# BQ24250.net
KiCad netlist of a schematic drawn in Altium Designer
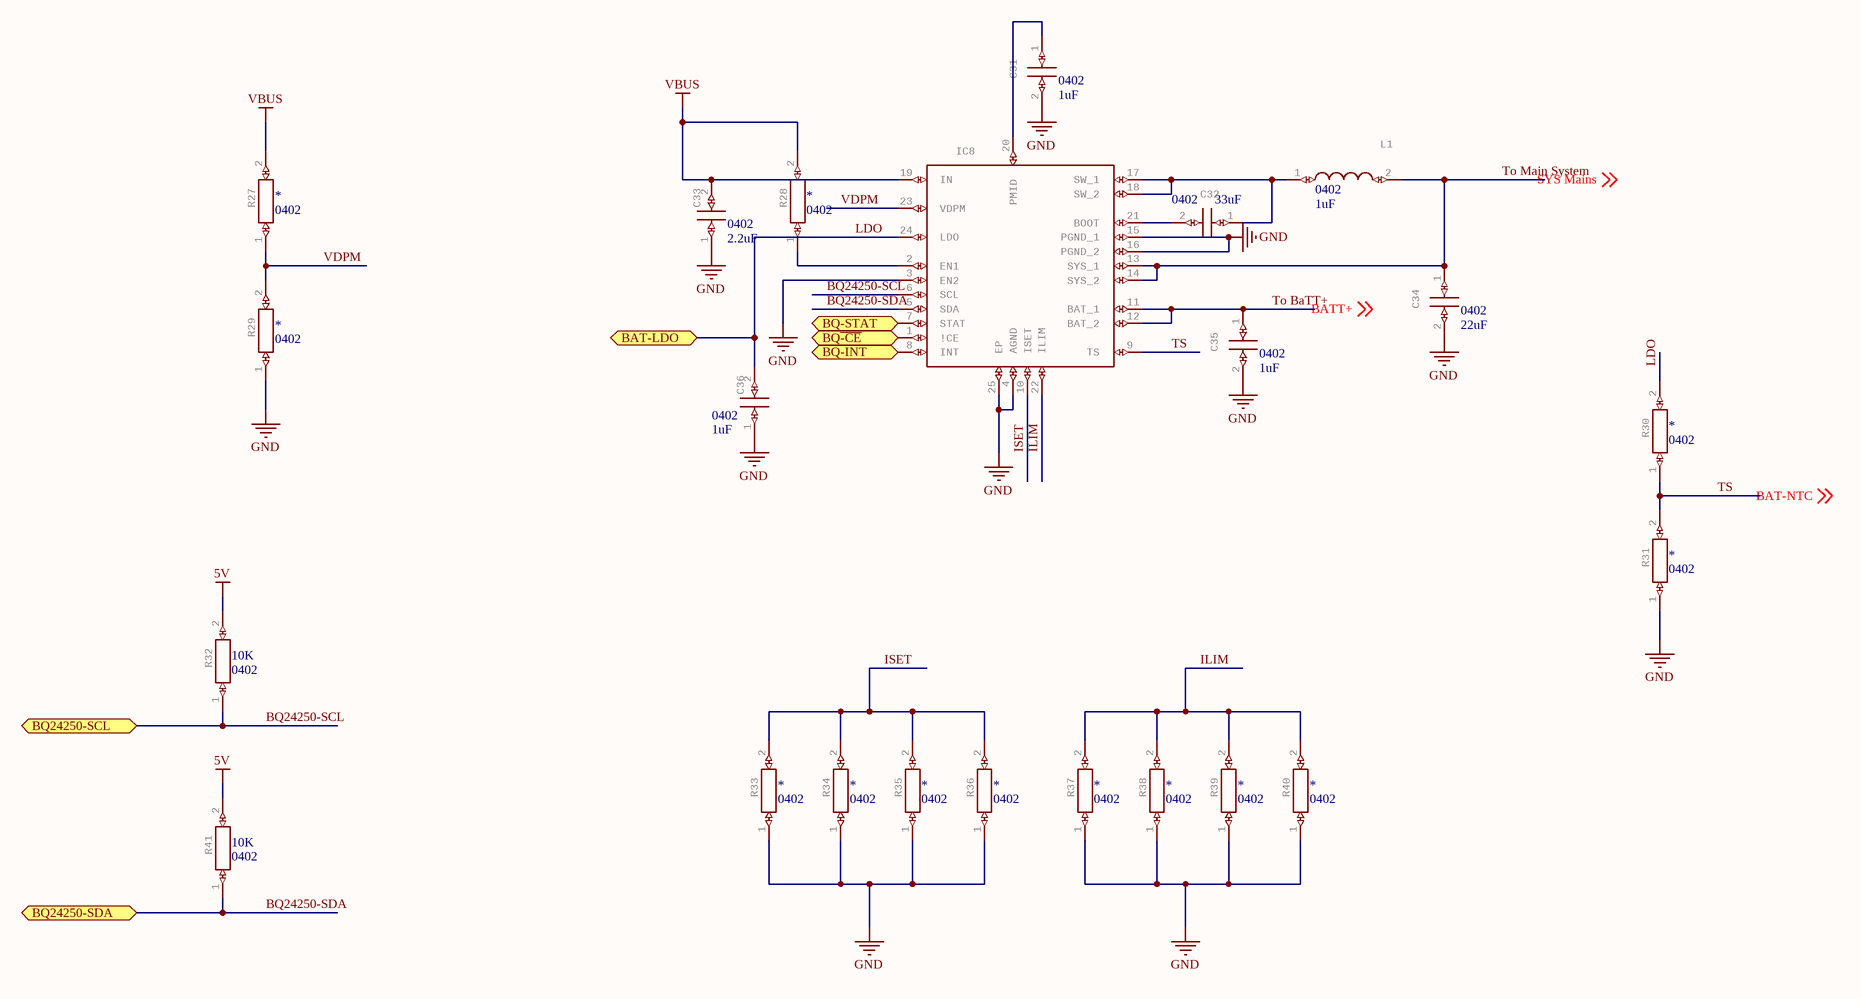
[diagram p0: BQ24250.SchDoc]

(export (version "E")
  (design (tool "Eeschema 10.0.6"))
  (components
    (comp (ref "C31")
      (value "1uF")
      (footprint "CAPC1005X56N")
      (fields
        (field (name "MANUFACTURER_PART_NUMBER") "04025C104KAT2A")
        (field (name "MOUSER_PART_NUMBER") "581-04025C104KAT2A")
        (field (name "PACKAGE") "0402")
        (field (name "Comment") "Multilayer Ceramic Capacitors MLCC - SMD/SMT 50V .1uF X7R 0402 10% Tol   Source:  Datasheet")
      )
      (libsource (lib "C0402-GP") (part "04025C104KAT2A"))
    )
    (comp (ref "C32")
      (value "33uF")
      (footprint "CAPC1005X56N")
      (fields
        (field (name "MANUFACTURER_PART_NUMBER") "04025C104KAT2A")
        (field (name "MOUSER_PART_NUMBER") "581-04025C104KAT2A")
        (field (name "PACKAGE") "0402")
        (field (name "Comment") "Multilayer Ceramic Capacitors MLCC - SMD/SMT 50V .1uF X7R 0402 10% Tol   Source:  Datasheet")
      )
      (libsource (lib "C0402-GP") (part "04025C104KAT2A"))
    )
    (comp (ref "C33")
      (value "2.2uF")
      (footprint "CAPC1005X56N")
      (fields
        (field (name "MANUFACTURER_PART_NUMBER") "04025C104KAT2A")
        (field (name "MOUSER_PART_NUMBER") "581-04025C104KAT2A")
        (field (name "PACKAGE") "0402")
        (field (name "Comment") "Multilayer Ceramic Capacitors MLCC - SMD/SMT 50V .1uF X7R 0402 10% Tol   Source:  Datasheet")
      )
      (libsource (lib "C0402-GP") (part "04025C104KAT2A"))
    )
    (comp (ref "C34")
      (value "22uF")
      (footprint "CAPC1005X56N")
      (fields
        (field (name "MANUFACTURER_PART_NUMBER") "04025C104KAT2A")
        (field (name "MOUSER_PART_NUMBER") "581-04025C104KAT2A")
        (field (name "PACKAGE") "0402")
        (field (name "Comment") "Multilayer Ceramic Capacitors MLCC - SMD/SMT 50V .1uF X7R 0402 10% Tol   Source:  Datasheet")
      )
      (libsource (lib "C0402-GP") (part "04025C104KAT2A"))
    )
    (comp (ref "C35")
      (value "1uF")
      (footprint "CAPC1005X56N")
      (fields
        (field (name "MANUFACTURER_PART_NUMBER") "04025C104KAT2A")
        (field (name "MOUSER_PART_NUMBER") "581-04025C104KAT2A")
        (field (name "PACKAGE") "0402")
        (field (name "Comment") "Multilayer Ceramic Capacitors MLCC - SMD/SMT 50V .1uF X7R 0402 10% Tol   Source:  Datasheet")
      )
      (libsource (lib "C0402-GP") (part "04025C104KAT2A"))
    )
    (comp (ref "C36")
      (value "1uF")
      (footprint "CAPC1005X56N")
      (fields
        (field (name "MANUFACTURER_PART_NUMBER") "04025C104KAT2A")
        (field (name "MOUSER_PART_NUMBER") "581-04025C104KAT2A")
        (field (name "PACKAGE") "0402")
        (field (name "Comment") "Multilayer Ceramic Capacitors MLCC - SMD/SMT 50V .1uF X7R 0402 10% Tol   Source:  Datasheet")
      )
      (libsource (lib "C0402-GP") (part "04025C104KAT2A"))
    )
    (comp (ref "IC8")
      (value "2A Single Input I2C/Standalone Switch-Mode Li-Ion Battery Charger   Source:  Datasheet")
      (footprint "QFN50P400X400X100-25N")
      (fields
        (field (name "MANUFACTURER_PART_NUMBER") "BQ24250RGER")
        (field (name "MOUSER_PART_NUMBER") "595-BQ24250RGER")
      )
      (libsource (lib "BQ24250RGER") (part "BQ24250RGER"))
    )
    (comp (ref "L1")
      (value "1uF")
      (footprint "INDC1005X55N")
      (fields
        (field (name "MANUFACTURER_PART_NUMBER") "MCEE1005T1R0MHN")
        (field (name "MOUSER_PART_NUMBER") "963-MCEE1005T1R0MHN")
        (field (name "PACKAGE") "0402")
        (field (name "Comment") "Fixed Inductors INDUCTOR,MCOIL HIGH CURRENT,1.0UH 20% ,T&R   Source:  Datasheet")
      )
      (libsource (lib "MCEE1005T1R0MHN") (part "MCEE1005T1R0MHN"))
    )
    (comp (ref "R27")
      (value "GENERAL PURPOSE CHIP RESISTORS   Source:  Datasheet")
      (footprint "RESC1005X40N")
      (fields
        (field (name "MANUFACTURER_PART_NUMBER") "RC0402FR-071KL")
        (field (name "MOUSER_PART_NUMBER") "603-RC0402FR-071KL")
        (field (name "ALTIUM_VALUE") "*")
        (field (name "PACKAGE") "0402")
      )
      (libsource (lib "R0402-GP") (part "RC0402FR-071KL"))
    )
    (comp (ref "R28")
      (value "GENERAL PURPOSE CHIP RESISTORS   Source:  Datasheet")
      (footprint "RESC1005X40N")
      (fields
        (field (name "MANUFACTURER_PART_NUMBER") "RC0402FR-071KL")
        (field (name "MOUSER_PART_NUMBER") "603-RC0402FR-071KL")
        (field (name "ALTIUM_VALUE") "*")
        (field (name "PACKAGE") "0402")
      )
      (libsource (lib "R0402-GP") (part "RC0402FR-071KL"))
    )
    (comp (ref "R29")
      (value "GENERAL PURPOSE CHIP RESISTORS   Source:  Datasheet")
      (footprint "RESC1005X40N")
      (fields
        (field (name "MANUFACTURER_PART_NUMBER") "RC0402FR-071KL")
        (field (name "MOUSER_PART_NUMBER") "603-RC0402FR-071KL")
        (field (name "ALTIUM_VALUE") "*")
        (field (name "PACKAGE") "0402")
      )
      (libsource (lib "R0402-GP") (part "RC0402FR-071KL"))
    )
    (comp (ref "R30")
      (value "GENERAL PURPOSE CHIP RESISTORS   Source:  Datasheet")
      (footprint "RESC1005X40N")
      (fields
        (field (name "MANUFACTURER_PART_NUMBER") "RC0402FR-071KL")
        (field (name "MOUSER_PART_NUMBER") "603-RC0402FR-071KL")
        (field (name "ALTIUM_VALUE") "*")
        (field (name "PACKAGE") "0402")
      )
      (libsource (lib "R0402-GP") (part "RC0402FR-071KL"))
    )
    (comp (ref "R31")
      (value "GENERAL PURPOSE CHIP RESISTORS   Source:  Datasheet")
      (footprint "RESC1005X40N")
      (fields
        (field (name "MANUFACTURER_PART_NUMBER") "RC0402FR-071KL")
        (field (name "MOUSER_PART_NUMBER") "603-RC0402FR-071KL")
        (field (name "ALTIUM_VALUE") "*")
        (field (name "PACKAGE") "0402")
      )
      (libsource (lib "R0402-GP") (part "RC0402FR-071KL"))
    )
    (comp (ref "R32")
      (value "10K")
      (footprint "RESC1005X40N")
      (fields
        (field (name "MANUFACTURER_PART_NUMBER") "RC0402FR-071KL")
        (field (name "MOUSER_PART_NUMBER") "603-RC0402FR-071KL")
        (field (name "PACKAGE") "0402")
        (field (name "Comment") "GENERAL PURPOSE CHIP RESISTORS   Source:  Datasheet")
      )
      (libsource (lib "R0402-GP") (part "RC0402FR-071KL"))
    )
    (comp (ref "R33")
      (value "GENERAL PURPOSE CHIP RESISTORS   Source:  Datasheet")
      (footprint "RESC1005X40N")
      (fields
        (field (name "MANUFACTURER_PART_NUMBER") "RC0402FR-071KL")
        (field (name "MOUSER_PART_NUMBER") "603-RC0402FR-071KL")
        (field (name "ALTIUM_VALUE") "*")
        (field (name "PACKAGE") "0402")
      )
      (libsource (lib "R0402-GP") (part "RC0402FR-071KL"))
    )
    (comp (ref "R34")
      (value "GENERAL PURPOSE CHIP RESISTORS   Source:  Datasheet")
      (footprint "RESC1005X40N")
      (fields
        (field (name "MANUFACTURER_PART_NUMBER") "RC0402FR-071KL")
        (field (name "MOUSER_PART_NUMBER") "603-RC0402FR-071KL")
        (field (name "ALTIUM_VALUE") "*")
        (field (name "PACKAGE") "0402")
      )
      (libsource (lib "R0402-GP") (part "RC0402FR-071KL"))
    )
    (comp (ref "R35")
      (value "GENERAL PURPOSE CHIP RESISTORS   Source:  Datasheet")
      (footprint "RESC1005X40N")
      (fields
        (field (name "MANUFACTURER_PART_NUMBER") "RC0402FR-071KL")
        (field (name "MOUSER_PART_NUMBER") "603-RC0402FR-071KL")
        (field (name "ALTIUM_VALUE") "*")
        (field (name "PACKAGE") "0402")
      )
      (libsource (lib "R0402-GP") (part "RC0402FR-071KL"))
    )
    (comp (ref "R36")
      (value "GENERAL PURPOSE CHIP RESISTORS   Source:  Datasheet")
      (footprint "RESC1005X40N")
      (fields
        (field (name "MANUFACTURER_PART_NUMBER") "RC0402FR-071KL")
        (field (name "MOUSER_PART_NUMBER") "603-RC0402FR-071KL")
        (field (name "ALTIUM_VALUE") "*")
        (field (name "PACKAGE") "0402")
      )
      (libsource (lib "R0402-GP") (part "RC0402FR-071KL"))
    )
    (comp (ref "R37")
      (value "GENERAL PURPOSE CHIP RESISTORS   Source:  Datasheet")
      (footprint "RESC1005X40N")
      (fields
        (field (name "MANUFACTURER_PART_NUMBER") "RC0402FR-071KL")
        (field (name "MOUSER_PART_NUMBER") "603-RC0402FR-071KL")
        (field (name "ALTIUM_VALUE") "*")
        (field (name "PACKAGE") "0402")
      )
      (libsource (lib "R0402-GP") (part "RC0402FR-071KL"))
    )
    (comp (ref "R38")
      (value "GENERAL PURPOSE CHIP RESISTORS   Source:  Datasheet")
      (footprint "RESC1005X40N")
      (fields
        (field (name "MANUFACTURER_PART_NUMBER") "RC0402FR-071KL")
        (field (name "MOUSER_PART_NUMBER") "603-RC0402FR-071KL")
        (field (name "ALTIUM_VALUE") "*")
        (field (name "PACKAGE") "0402")
      )
      (libsource (lib "R0402-GP") (part "RC0402FR-071KL"))
    )
    (comp (ref "R39")
      (value "GENERAL PURPOSE CHIP RESISTORS   Source:  Datasheet")
      (footprint "RESC1005X40N")
      (fields
        (field (name "MANUFACTURER_PART_NUMBER") "RC0402FR-071KL")
        (field (name "MOUSER_PART_NUMBER") "603-RC0402FR-071KL")
        (field (name "ALTIUM_VALUE") "*")
        (field (name "PACKAGE") "0402")
      )
      (libsource (lib "R0402-GP") (part "RC0402FR-071KL"))
    )
    (comp (ref "R40")
      (value "GENERAL PURPOSE CHIP RESISTORS   Source:  Datasheet")
      (footprint "RESC1005X40N")
      (fields
        (field (name "MANUFACTURER_PART_NUMBER") "RC0402FR-071KL")
        (field (name "MOUSER_PART_NUMBER") "603-RC0402FR-071KL")
        (field (name "ALTIUM_VALUE") "*")
        (field (name "PACKAGE") "0402")
      )
      (libsource (lib "R0402-GP") (part "RC0402FR-071KL"))
    )
    (comp (ref "R41")
      (value "10K")
      (footprint "RESC1005X40N")
      (fields
        (field (name "MANUFACTURER_PART_NUMBER") "RC0402FR-071KL")
        (field (name "MOUSER_PART_NUMBER") "603-RC0402FR-071KL")
        (field (name "PACKAGE") "0402")
        (field (name "Comment") "GENERAL PURPOSE CHIP RESISTORS   Source:  Datasheet")
      )
      (libsource (lib "R0402-GP") (part "RC0402FR-071KL"))
    )
  )
  (nets
    (net (code "1") (name "/BQ-INT") (class "Default")
      (node (ref "IC8") (pin "8") (pinfunction "INT_8") (pintype "bidirectional"))
    )
    (net (code "2") (name "/BQ-STAT") (class "Default")
      (node (ref "IC8") (pin "7") (pinfunction "STAT_7") (pintype "bidirectional"))
    )
    (net (code "3") (name "/BQ24250-SCL") (class "Default")
      (node (ref "IC8") (pin "6") (pinfunction "SCL_6") (pintype "bidirectional"))
      (node (ref "R32") (pin "1") (pinfunction "1_1") (pintype "bidirectional"))
    )
    (net (code "4") (name "/BQ24250-SDA") (class "Default")
      (node (ref "IC8") (pin "5") (pinfunction "SDA_5") (pintype "bidirectional"))
      (node (ref "R41") (pin "1") (pinfunction "1_1") (pintype "bidirectional"))
    )
    (net (code "5") (name "/BQ~{-CE}") (class "Default")
      (node (ref "IC8") (pin "1") (pinfunction "!CE_1") (pintype "bidirectional"))
    )
    (net (code "6") (name "/ILIM") (class "Default")
      (node (ref "IC8") (pin "22") (pinfunction "ILIM_22") (pintype "bidirectional"))
      (node (ref "R37") (pin "2") (pinfunction "2_2") (pintype "bidirectional"))
      (node (ref "R38") (pin "2") (pinfunction "2_2") (pintype "bidirectional"))
      (node (ref "R39") (pin "2") (pinfunction "2_2") (pintype "bidirectional"))
      (node (ref "R40") (pin "2") (pinfunction "2_2") (pintype "bidirectional"))
    )
    (net (code "7") (name "/ISET") (class "Default")
      (node (ref "IC8") (pin "10") (pinfunction "ISET_10") (pintype "bidirectional"))
      (node (ref "R33") (pin "2") (pinfunction "2_2") (pintype "bidirectional"))
      (node (ref "R34") (pin "2") (pinfunction "2_2") (pintype "bidirectional"))
      (node (ref "R35") (pin "2") (pinfunction "2_2") (pintype "bidirectional"))
      (node (ref "R36") (pin "2") (pinfunction "2_2") (pintype "bidirectional"))
    )
    (net (code "8") (name "/LDO") (class "Default")
      (node (ref "C36") (pin "2") (pinfunction "2_2") (pintype "bidirectional"))
      (node (ref "IC8") (pin "24") (pinfunction "LDO_24") (pintype "bidirectional"))
      (node (ref "R30") (pin "2") (pinfunction "2_2") (pintype "bidirectional"))
    )
    (net (code "9") (name "/TS") (class "Default")
      (node (ref "IC8") (pin "9") (pinfunction "TS_9") (pintype "bidirectional"))
      (node (ref "R30") (pin "1") (pinfunction "1_1") (pintype "bidirectional"))
      (node (ref "R31") (pin "2") (pinfunction "2_2") (pintype "bidirectional"))
    )
    (net (code "10") (name "/To BaTT+") (class "Default")
      (node (ref "C35") (pin "1") (pinfunction "1_1") (pintype "bidirectional"))
      (node (ref "IC8") (pin "11") (pinfunction "BAT_1_11") (pintype "bidirectional"))
      (node (ref "IC8") (pin "12") (pinfunction "BAT_2_12") (pintype "bidirectional"))
    )
    (net (code "11") (name "/To Main System") (class "Default")
      (node (ref "C34") (pin "1") (pinfunction "1_1") (pintype "bidirectional"))
      (node (ref "IC8") (pin "13") (pinfunction "SYS_1_13") (pintype "bidirectional"))
      (node (ref "IC8") (pin "14") (pinfunction "SYS_2_14") (pintype "bidirectional"))
      (node (ref "L1") (pin "2") (pinfunction "2_2") (pintype "bidirectional"))
    )
    (net (code "12") (name "/VDPM") (class "Default")
      (node (ref "IC8") (pin "23") (pinfunction "VDPM_23") (pintype "bidirectional"))
      (node (ref "R27") (pin "1") (pinfunction "1_1") (pintype "bidirectional"))
      (node (ref "R29") (pin "2") (pinfunction "2_2") (pintype "bidirectional"))
    )
    (net (code "13") (name "5V") (class "Default")
      (node (ref "R32") (pin "2") (pinfunction "2_2") (pintype "bidirectional"))
      (node (ref "R41") (pin "2") (pinfunction "2_2") (pintype "bidirectional"))
    )
    (net (code "16") (name "GND") (class "Default")
      (node (ref "C31") (pin "2") (pinfunction "2_2") (pintype "bidirectional"))
      (node (ref "C33") (pin "1") (pinfunction "1_1") (pintype "bidirectional"))
      (node (ref "C34") (pin "2") (pinfunction "2_2") (pintype "bidirectional"))
      (node (ref "C35") (pin "2") (pinfunction "2_2") (pintype "bidirectional"))
      (node (ref "C36") (pin "1") (pinfunction "1_1") (pintype "bidirectional"))
      (node (ref "IC8") (pin "15") (pinfunction "PGND_1_15") (pintype "bidirectional"))
      (node (ref "IC8") (pin "16") (pinfunction "PGND_2_16") (pintype "bidirectional"))
      (node (ref "IC8") (pin "25") (pinfunction "EP_25") (pintype "bidirectional"))
      (node (ref "IC8") (pin "3") (pinfunction "EN2_3") (pintype "bidirectional"))
      (node (ref "IC8") (pin "4") (pinfunction "AGND_4") (pintype "bidirectional"))
      (node (ref "R29") (pin "1") (pinfunction "1_1") (pintype "bidirectional"))
      (node (ref "R31") (pin "1") (pinfunction "1_1") (pintype "bidirectional"))
      (node (ref "R33") (pin "1") (pinfunction "1_1") (pintype "bidirectional"))
      (node (ref "R34") (pin "1") (pinfunction "1_1") (pintype "bidirectional"))
      (node (ref "R35") (pin "1") (pinfunction "1_1") (pintype "bidirectional"))
      (node (ref "R36") (pin "1") (pinfunction "1_1") (pintype "bidirectional"))
      (node (ref "R37") (pin "1") (pinfunction "1_1") (pintype "bidirectional"))
      (node (ref "R38") (pin "1") (pinfunction "1_1") (pintype "bidirectional"))
      (node (ref "R39") (pin "1") (pinfunction "1_1") (pintype "bidirectional"))
      (node (ref "R40") (pin "1") (pinfunction "1_1") (pintype "bidirectional"))
    )
    (net (code "17") (name "Net-(IC8-BOOT)") (class "Default")
      (node (ref "C32") (pin "2") (pinfunction "2_2") (pintype "bidirectional"))
      (node (ref "IC8") (pin "21") (pinfunction "BOOT_21") (pintype "bidirectional"))
    )
    (net (code "18") (name "Net-(IC8-EN1)") (class "Default")
      (node (ref "IC8") (pin "2") (pinfunction "EN1_2") (pintype "bidirectional"))
      (node (ref "R28") (pin "1") (pinfunction "1_1") (pintype "bidirectional"))
    )
    (net (code "19") (name "Net-(IC8-PMID)") (class "Default")
      (node (ref "C31") (pin "1") (pinfunction "1_1") (pintype "bidirectional"))
      (node (ref "IC8") (pin "20") (pinfunction "PMID_20") (pintype "bidirectional"))
    )
    (net (code "20") (name "Net-(IC8-SW_1)") (class "Default")
      (node (ref "C32") (pin "1") (pinfunction "1_1") (pintype "bidirectional"))
      (node (ref "IC8") (pin "17") (pinfunction "SW_1_17") (pintype "bidirectional"))
      (node (ref "IC8") (pin "18") (pinfunction "SW_2_18") (pintype "bidirectional"))
      (node (ref "L1") (pin "1") (pinfunction "1_1") (pintype "bidirectional"))
    )
    (net (code "22") (name "VBUS") (class "Default")
      (node (ref "C33") (pin "2") (pinfunction "2_2") (pintype "bidirectional"))
      (node (ref "IC8") (pin "19") (pinfunction "IN_19") (pintype "bidirectional"))
      (node (ref "R27") (pin "2") (pinfunction "2_2") (pintype "bidirectional"))
      (node (ref "R28") (pin "2") (pinfunction "2_2") (pintype "bidirectional"))
    )
  )
)
